# ChuanGanQi.net
KiCad netlist of a schematic drawn in Altium Designer
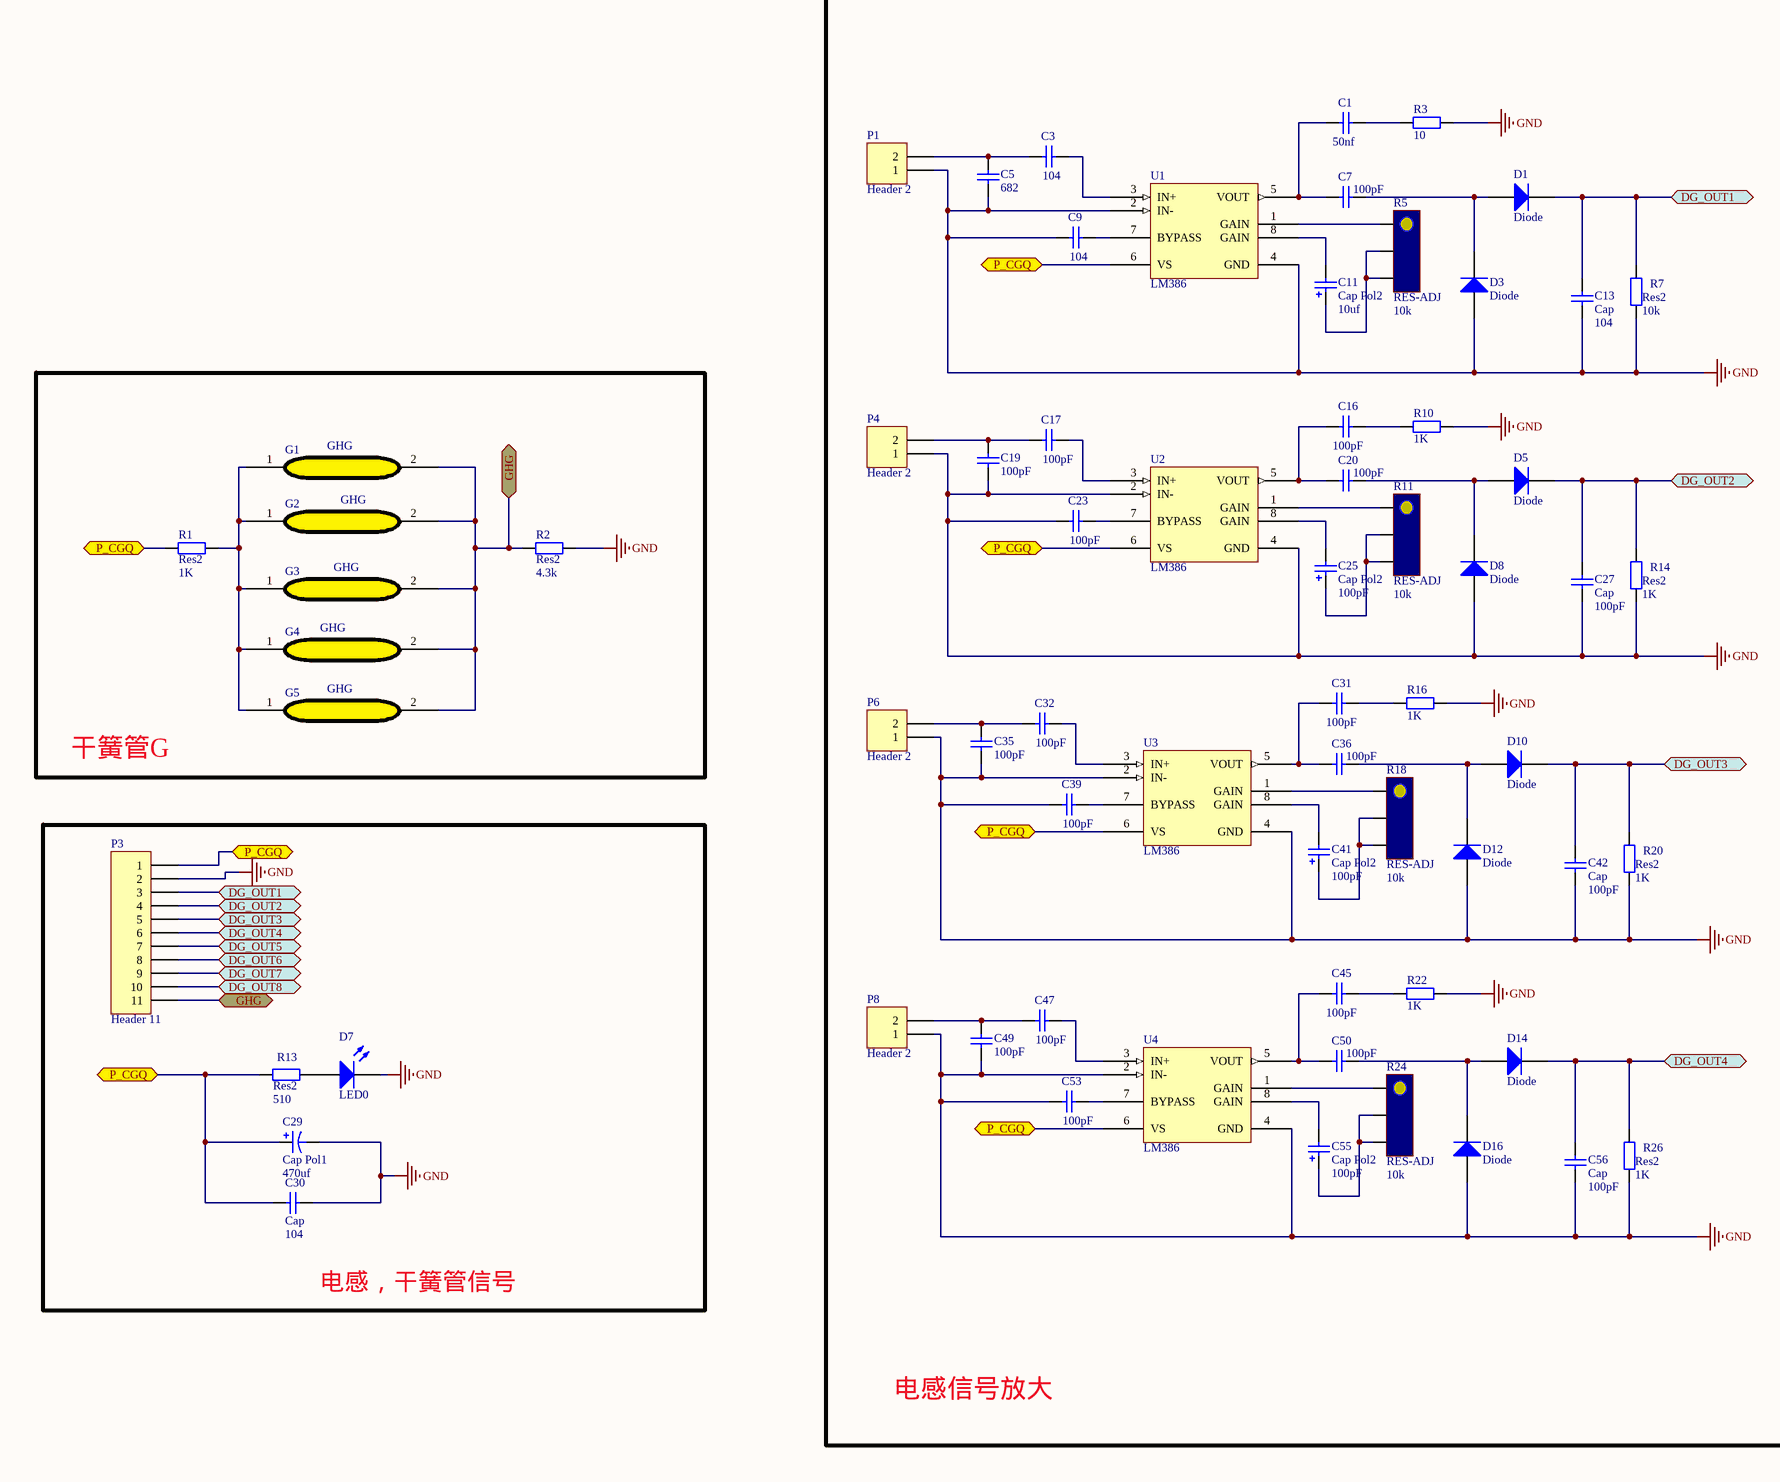
[diagram p0: ChuanGanQi.SchDoc, left]
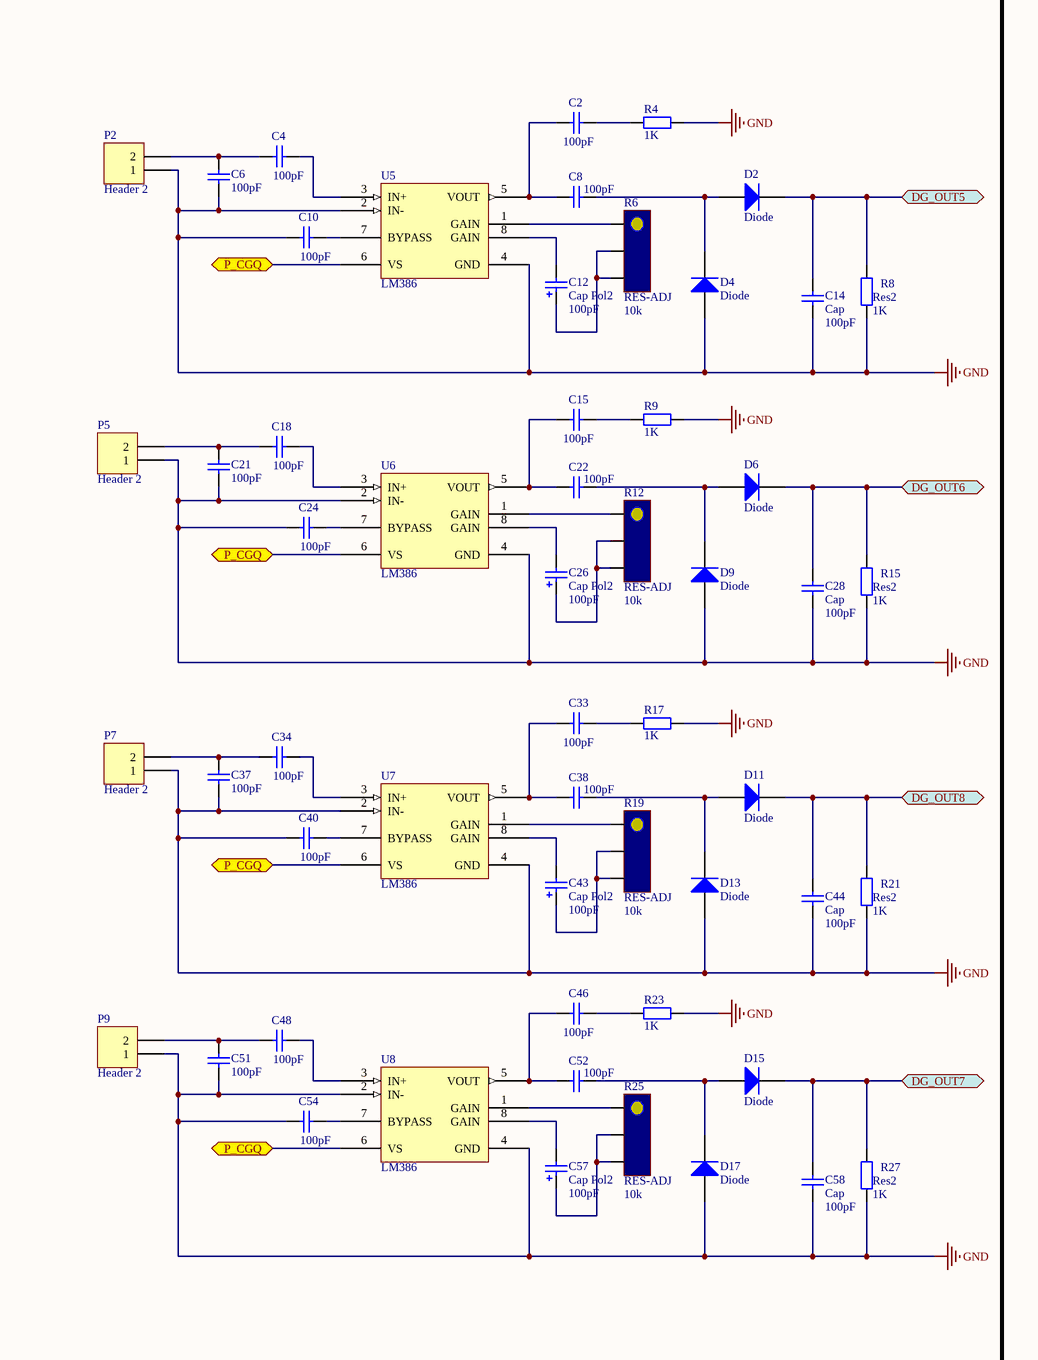
[diagram p1: ChuanGanQi.SchDoc, right]

(export (version "E")
  (design (tool "Eeschema 10.0.6"))
  (components
    (comp (ref "C1")
      (value "50nf")
      (footprint "C-0805")
      (description "Capacitor")
      (fields (field (name "Comment") "Cap"))
      (libsource (lib "Miscellaneous Devices") (part "Cap"))
    )
    (comp (ref "C2")
      (value "100pF")
      (footprint "C-0805")
      (description "Capacitor")
      (fields (field (name "Comment") "Cap"))
      (libsource (lib "Miscellaneous Devices") (part "Cap"))
    )
    (comp (ref "C3")
      (value "104")
      (footprint "C-0805")
      (description "Capacitor")
      (fields (field (name "Comment") "Cap"))
      (libsource (lib "Miscellaneous Devices") (part "Cap"))
    )
    (comp (ref "C4")
      (value "100pF")
      (footprint "C-0805")
      (description "Capacitor")
      (fields (field (name "Comment") "Cap"))
      (libsource (lib "Miscellaneous Devices") (part "Cap"))
    )
    (comp (ref "C5")
      (value "682")
      (footprint "C-0805")
      (description "Capacitor")
      (fields (field (name "Comment") "Cap"))
      (libsource (lib "Miscellaneous Devices") (part "Cap"))
    )
    (comp (ref "C6")
      (value "100pF")
      (footprint "C-0805")
      (description "Capacitor")
      (fields (field (name "Comment") "Cap"))
      (libsource (lib "Miscellaneous Devices") (part "Cap"))
    )
    (comp (ref "C7")
      (value "100pF")
      (footprint "C-0805")
      (description "Capacitor")
      (fields (field (name "Comment") "Cap"))
      (libsource (lib "Miscellaneous Devices") (part "Cap"))
    )
    (comp (ref "C8")
      (value "100pF")
      (footprint "C-0805")
      (description "Capacitor")
      (fields (field (name "Comment") "Cap"))
      (libsource (lib "Miscellaneous Devices") (part "Cap"))
    )
    (comp (ref "C9")
      (value "104")
      (footprint "C-0805")
      (description "Capacitor")
      (fields (field (name "Comment") "Cap"))
      (libsource (lib "Miscellaneous Devices") (part "Cap"))
    )
    (comp (ref "C10")
      (value "100pF")
      (footprint "C-0805")
      (description "Capacitor")
      (fields (field (name "Comment") "Cap"))
      (libsource (lib "Miscellaneous Devices") (part "Cap"))
    )
    (comp (ref "C11")
      (value "Cap Pol2")
      (footprint "C-0805")
      (description "Polarized Capacitor (Axial)")
      (fields (field (name "ALTIUM_VALUE") "10uf"))
      (libsource (lib "Miscellaneous Devices") (part "Cap Pol2"))
    )
    (comp (ref "C12")
      (value "Cap Pol2")
      (footprint "C-0805")
      (description "Polarized Capacitor (Axial)")
      (fields (field (name "ALTIUM_VALUE") "100pF"))
      (libsource (lib "Miscellaneous Devices") (part "Cap Pol2"))
    )
    (comp (ref "C13")
      (value "Cap")
      (footprint "C-0805")
      (description "Capacitor")
      (fields (field (name "ALTIUM_VALUE") "104"))
      (libsource (lib "Miscellaneous Devices") (part "Cap"))
    )
    (comp (ref "C14")
      (value "Cap")
      (footprint "C-0805")
      (description "Capacitor")
      (fields (field (name "ALTIUM_VALUE") "100pF"))
      (libsource (lib "Miscellaneous Devices") (part "Cap"))
    )
    (comp (ref "C15")
      (value "100pF")
      (footprint "C-0805")
      (description "Capacitor")
      (fields (field (name "Comment") "Cap"))
      (libsource (lib "Miscellaneous Devices") (part "Cap"))
    )
    (comp (ref "C16")
      (value "100pF")
      (footprint "C-0805")
      (description "Capacitor")
      (fields (field (name "Comment") "Cap"))
      (libsource (lib "Miscellaneous Devices") (part "Cap"))
    )
    (comp (ref "C17")
      (value "100pF")
      (footprint "C-0805")
      (description "Capacitor")
      (fields (field (name "Comment") "Cap"))
      (libsource (lib "Miscellaneous Devices") (part "Cap"))
    )
    (comp (ref "C18")
      (value "100pF")
      (footprint "C-0805")
      (description "Capacitor")
      (fields (field (name "Comment") "Cap"))
      (libsource (lib "Miscellaneous Devices") (part "Cap"))
    )
    (comp (ref "C19")
      (value "100pF")
      (footprint "C-0805")
      (description "Capacitor")
      (fields (field (name "Comment") "Cap"))
      (libsource (lib "Miscellaneous Devices") (part "Cap"))
    )
    (comp (ref "C20")
      (value "100pF")
      (footprint "C-0805")
      (description "Capacitor")
      (fields (field (name "Comment") "Cap"))
      (libsource (lib "Miscellaneous Devices") (part "Cap"))
    )
    (comp (ref "C21")
      (value "100pF")
      (footprint "C-0805")
      (description "Capacitor")
      (fields (field (name "Comment") "Cap"))
      (libsource (lib "Miscellaneous Devices") (part "Cap"))
    )
    (comp (ref "C22")
      (value "100pF")
      (footprint "C-0805")
      (description "Capacitor")
      (fields (field (name "Comment") "Cap"))
      (libsource (lib "Miscellaneous Devices") (part "Cap"))
    )
    (comp (ref "C23")
      (value "100pF")
      (footprint "C-0805")
      (description "Capacitor")
      (fields (field (name "Comment") "Cap"))
      (libsource (lib "Miscellaneous Devices") (part "Cap"))
    )
    (comp (ref "C24")
      (value "100pF")
      (footprint "C-0805")
      (description "Capacitor")
      (fields (field (name "Comment") "Cap"))
      (libsource (lib "Miscellaneous Devices") (part "Cap"))
    )
    (comp (ref "C25")
      (value "Cap Pol2")
      (footprint "C-0805")
      (description "Polarized Capacitor (Axial)")
      (fields (field (name "ALTIUM_VALUE") "100pF"))
      (libsource (lib "Miscellaneous Devices") (part "Cap Pol2"))
    )
    (comp (ref "C26")
      (value "Cap Pol2")
      (footprint "C-0805")
      (description "Polarized Capacitor (Axial)")
      (fields (field (name "ALTIUM_VALUE") "100pF"))
      (libsource (lib "Miscellaneous Devices") (part "Cap Pol2"))
    )
    (comp (ref "C27")
      (value "Cap")
      (footprint "C-0805")
      (description "Capacitor")
      (fields (field (name "ALTIUM_VALUE") "100pF"))
      (libsource (lib "Miscellaneous Devices") (part "Cap"))
    )
    (comp (ref "C28")
      (value "Cap")
      (footprint "C-0805")
      (description "Capacitor")
      (fields (field (name "ALTIUM_VALUE") "100pF"))
      (libsource (lib "Miscellaneous Devices") (part "Cap"))
    )
    (comp (ref "C29")
      (value "Cap Pol1")
      (footprint "1206")
      (description "Polarized Capacitor (Radial)")
      (fields (field (name "ALTIUM_VALUE") "470uf"))
      (libsource (lib "Miscellaneous Devices") (part "Cap Pol1"))
    )
    (comp (ref "C30")
      (value "Cap")
      (footprint "C-0805")
      (description "Capacitor")
      (fields (field (name "ALTIUM_VALUE") "104"))
      (libsource (lib "Miscellaneous Devices") (part "Cap"))
    )
    (comp (ref "C31")
      (value "100pF")
      (footprint "C-0805")
      (description "Capacitor")
      (fields (field (name "Comment") "Cap"))
      (libsource (lib "Miscellaneous Devices") (part "Cap"))
    )
    (comp (ref "C32")
      (value "100pF")
      (footprint "C-0805")
      (description "Capacitor")
      (fields (field (name "Comment") "Cap"))
      (libsource (lib "Miscellaneous Devices") (part "Cap"))
    )
    (comp (ref "C33")
      (value "100pF")
      (footprint "C-0805")
      (description "Capacitor")
      (fields (field (name "Comment") "Cap"))
      (libsource (lib "Miscellaneous Devices") (part "Cap"))
    )
    (comp (ref "C34")
      (value "100pF")
      (footprint "C-0805")
      (description "Capacitor")
      (fields (field (name "Comment") "Cap"))
      (libsource (lib "Miscellaneous Devices") (part "Cap"))
    )
    (comp (ref "C35")
      (value "100pF")
      (footprint "C-0805")
      (description "Capacitor")
      (fields (field (name "Comment") "Cap"))
      (libsource (lib "Miscellaneous Devices") (part "Cap"))
    )
    (comp (ref "C36")
      (value "100pF")
      (footprint "C-0805")
      (description "Capacitor")
      (fields (field (name "Comment") "Cap"))
      (libsource (lib "Miscellaneous Devices") (part "Cap"))
    )
    (comp (ref "C37")
      (value "100pF")
      (footprint "C-0805")
      (description "Capacitor")
      (fields (field (name "Comment") "Cap"))
      (libsource (lib "Miscellaneous Devices") (part "Cap"))
    )
    (comp (ref "C38")
      (value "100pF")
      (footprint "C-0805")
      (description "Capacitor")
      (fields (field (name "Comment") "Cap"))
      (libsource (lib "Miscellaneous Devices") (part "Cap"))
    )
    (comp (ref "C39")
      (value "100pF")
      (footprint "C-0805")
      (description "Capacitor")
      (fields (field (name "Comment") "Cap"))
      (libsource (lib "Miscellaneous Devices") (part "Cap"))
    )
    (comp (ref "C40")
      (value "100pF")
      (footprint "C-0805")
      (description "Capacitor")
      (fields (field (name "Comment") "Cap"))
      (libsource (lib "Miscellaneous Devices") (part "Cap"))
    )
    (comp (ref "C41")
      (value "Cap Pol2")
      (footprint "C-0805")
      (description "Polarized Capacitor (Axial)")
      (fields (field (name "ALTIUM_VALUE") "100pF"))
      (libsource (lib "Miscellaneous Devices") (part "Cap Pol2"))
    )
    (comp (ref "C42")
      (value "Cap")
      (footprint "C-0805")
      (description "Capacitor")
      (fields (field (name "ALTIUM_VALUE") "100pF"))
      (libsource (lib "Miscellaneous Devices") (part "Cap"))
    )
    (comp (ref "C43")
      (value "Cap Pol2")
      (footprint "C-0805")
      (description "Polarized Capacitor (Axial)")
      (fields (field (name "ALTIUM_VALUE") "100pF"))
      (libsource (lib "Miscellaneous Devices") (part "Cap Pol2"))
    )
    (comp (ref "C44")
      (value "Cap")
      (footprint "C-0805")
      (description "Capacitor")
      (fields (field (name "ALTIUM_VALUE") "100pF"))
      (libsource (lib "Miscellaneous Devices") (part "Cap"))
    )
    (comp (ref "C45")
      (value "100pF")
      (footprint "C-0805")
      (description "Capacitor")
      (fields (field (name "Comment") "Cap"))
      (libsource (lib "Miscellaneous Devices") (part "Cap"))
    )
    (comp (ref "C46")
      (value "100pF")
      (footprint "C-0805")
      (description "Capacitor")
      (fields (field (name "Comment") "Cap"))
      (libsource (lib "Miscellaneous Devices") (part "Cap"))
    )
    (comp (ref "C47")
      (value "100pF")
      (footprint "C-0805")
      (description "Capacitor")
      (fields (field (name "Comment") "Cap"))
      (libsource (lib "Miscellaneous Devices") (part "Cap"))
    )
    (comp (ref "C48")
      (value "100pF")
      (footprint "C-0805")
      (description "Capacitor")
      (fields (field (name "Comment") "Cap"))
      (libsource (lib "Miscellaneous Devices") (part "Cap"))
    )
    (comp (ref "C49")
      (value "100pF")
      (footprint "C-0805")
      (description "Capacitor")
      (fields (field (name "Comment") "Cap"))
      (libsource (lib "Miscellaneous Devices") (part "Cap"))
    )
    (comp (ref "C50")
      (value "100pF")
      (footprint "C-0805")
      (description "Capacitor")
      (fields (field (name "Comment") "Cap"))
      (libsource (lib "Miscellaneous Devices") (part "Cap"))
    )
    (comp (ref "C51")
      (value "100pF")
      (footprint "C-0805")
      (description "Capacitor")
      (fields (field (name "Comment") "Cap"))
      (libsource (lib "Miscellaneous Devices") (part "Cap"))
    )
    (comp (ref "C52")
      (value "100pF")
      (footprint "C-0805")
      (description "Capacitor")
      (fields (field (name "Comment") "Cap"))
      (libsource (lib "Miscellaneous Devices") (part "Cap"))
    )
    (comp (ref "C53")
      (value "100pF")
      (footprint "C-0805")
      (description "Capacitor")
      (fields (field (name "Comment") "Cap"))
      (libsource (lib "Miscellaneous Devices") (part "Cap"))
    )
    (comp (ref "C54")
      (value "100pF")
      (footprint "C-0805")
      (description "Capacitor")
      (fields (field (name "Comment") "Cap"))
      (libsource (lib "Miscellaneous Devices") (part "Cap"))
    )
    (comp (ref "C55")
      (value "Cap Pol2")
      (footprint "C-0805")
      (description "Polarized Capacitor (Axial)")
      (fields (field (name "ALTIUM_VALUE") "100pF"))
      (libsource (lib "Miscellaneous Devices") (part "Cap Pol2"))
    )
    (comp (ref "C56")
      (value "Cap")
      (footprint "C-0805")
      (description "Capacitor")
      (fields (field (name "ALTIUM_VALUE") "100pF"))
      (libsource (lib "Miscellaneous Devices") (part "Cap"))
    )
    (comp (ref "C57")
      (value "Cap Pol2")
      (footprint "C-0805")
      (description "Polarized Capacitor (Axial)")
      (fields (field (name "ALTIUM_VALUE") "100pF"))
      (libsource (lib "Miscellaneous Devices") (part "Cap Pol2"))
    )
    (comp (ref "C58")
      (value "Cap")
      (footprint "C-0805")
      (description "Capacitor")
      (fields (field (name "ALTIUM_VALUE") "100pF"))
      (libsource (lib "Miscellaneous Devices") (part "Cap"))
    )
    (comp (ref "D1")
      (value "Diode")
      (footprint "DO214AA")
      (description "Default Diode")
      (libsource (lib "Miscellaneous Devices") (part "Diode"))
    )
    (comp (ref "D2")
      (value "Diode")
      (footprint "DO214AA")
      (description "Default Diode")
      (libsource (lib "Miscellaneous Devices") (part "Diode"))
    )
    (comp (ref "D3")
      (value "Diode")
      (footprint "DO214AA")
      (description "Default Diode")
      (libsource (lib "Miscellaneous Devices") (part "Diode"))
    )
    (comp (ref "D4")
      (value "Diode")
      (footprint "DO214AA")
      (description "Default Diode")
      (libsource (lib "Miscellaneous Devices") (part "Diode"))
    )
    (comp (ref "D5")
      (value "Diode")
      (footprint "DO214AA")
      (description "Default Diode")
      (libsource (lib "Miscellaneous Devices") (part "Diode"))
    )
    (comp (ref "D6")
      (value "Diode")
      (footprint "DO214AA")
      (description "Default Diode")
      (libsource (lib "Miscellaneous Devices") (part "Diode"))
    )
    (comp (ref "D7")
      (value "LED0")
      (footprint "6-0805_N")
      (description "Typical INFRARED GaAs LED")
      (libsource (lib "Miscellaneous Devices") (part "LED0"))
    )
    (comp (ref "D8")
      (value "Diode")
      (footprint "DO214AA")
      (description "Default Diode")
      (libsource (lib "Miscellaneous Devices") (part "Diode"))
    )
    (comp (ref "D9")
      (value "Diode")
      (footprint "DO214AA")
      (description "Default Diode")
      (libsource (lib "Miscellaneous Devices") (part "Diode"))
    )
    (comp (ref "D10")
      (value "Diode")
      (footprint "DO214AA")
      (description "Default Diode")
      (libsource (lib "Miscellaneous Devices") (part "Diode"))
    )
    (comp (ref "D11")
      (value "Diode")
      (footprint "DO214AA")
      (description "Default Diode")
      (libsource (lib "Miscellaneous Devices") (part "Diode"))
    )
    (comp (ref "D12")
      (value "Diode")
      (footprint "DO214AA")
      (description "Default Diode")
      (libsource (lib "Miscellaneous Devices") (part "Diode"))
    )
    (comp (ref "D13")
      (value "Diode")
      (footprint "DO214AA")
      (description "Default Diode")
      (libsource (lib "Miscellaneous Devices") (part "Diode"))
    )
    (comp (ref "D14")
      (value "Diode")
      (footprint "DO214AA")
      (description "Default Diode")
      (libsource (lib "Miscellaneous Devices") (part "Diode"))
    )
    (comp (ref "D15")
      (value "Diode")
      (footprint "DO214AA")
      (description "Default Diode")
      (libsource (lib "Miscellaneous Devices") (part "Diode"))
    )
    (comp (ref "D16")
      (value "Diode")
      (footprint "DO214AA")
      (description "Default Diode")
      (libsource (lib "Miscellaneous Devices") (part "Diode"))
    )
    (comp (ref "D17")
      (value "Diode")
      (footprint "DO214AA")
      (description "Default Diode")
      (libsource (lib "Miscellaneous Devices") (part "Diode"))
    )
    (comp (ref "G1") (value "GHG") (footprint "GHG_MIN") (libsource (lib "常用封装") (part "GHG")))
    (comp (ref "G2") (value "GHG") (footprint "GHG_MIN") (libsource (lib "常用封装") (part "GHG")))
    (comp (ref "G3") (value "GHG") (footprint "GHG_MIN") (libsource (lib "常用封装") (part "GHG")))
    (comp (ref "G4") (value "GHG") (footprint "GHG_MIN") (libsource (lib "常用封装") (part "GHG")))
    (comp (ref "G5") (value "GHG") (footprint "GHG_MIN") (libsource (lib "常用封装") (part "GHG")))
    (comp (ref "P1")
      (value "Header 2")
      (footprint "HDR1X2")
      (description "Header, 2-Pin")
      (libsource (lib "Miscellaneous Connectors") (part "Header 2"))
    )
    (comp (ref "P2")
      (value "Header 2")
      (footprint "HDR1X2")
      (description "Header, 2-Pin")
      (libsource (lib "Miscellaneous Connectors") (part "Header 2"))
    )
    (comp (ref "P3")
      (value "Header 11")
      (footprint "HDR1X11")
      (description "Header, 11-Pin")
      (libsource (lib "Miscellaneous Connectors") (part "Header 11"))
    )
    (comp (ref "P4")
      (value "Header 2")
      (footprint "HDR1X2")
      (description "Header, 2-Pin")
      (libsource (lib "Miscellaneous Connectors") (part "Header 2"))
    )
    (comp (ref "P5")
      (value "Header 2")
      (footprint "HDR1X2")
      (description "Header, 2-Pin")
      (libsource (lib "Miscellaneous Connectors") (part "Header 2"))
    )
    (comp (ref "P6")
      (value "Header 2")
      (footprint "HDR1X2")
      (description "Header, 2-Pin")
      (libsource (lib "Miscellaneous Connectors") (part "Header 2"))
    )
    (comp (ref "P7")
      (value "Header 2")
      (footprint "HDR1X2")
      (description "Header, 2-Pin")
      (libsource (lib "Miscellaneous Connectors") (part "Header 2"))
    )
    (comp (ref "P8")
      (value "Header 2")
      (footprint "HDR1X2")
      (description "Header, 2-Pin")
      (libsource (lib "Miscellaneous Connectors") (part "Header 2"))
    )
    (comp (ref "P9")
      (value "Header 2")
      (footprint "HDR1X2")
      (description "Header, 2-Pin")
      (libsource (lib "Miscellaneous Connectors") (part "Header 2"))
    )
    (comp (ref "R1")
      (value "Res2")
      (footprint "0805")
      (description "Resistor")
      (fields (field (name "ALTIUM_VALUE") "1K"))
      (libsource (lib "Miscellaneous Devices") (part "Res2"))
    )
    (comp (ref "R2")
      (value "Res2")
      (footprint "0805")
      (description "Resistor")
      (fields (field (name "ALTIUM_VALUE") "4.3k"))
      (libsource (lib "Miscellaneous Devices") (part "Res2"))
    )
    (comp (ref "R3")
      (value "10")
      (footprint "0805")
      (description "Resistor")
      (fields (field (name "Comment") "Res2"))
      (libsource (lib "Miscellaneous Devices") (part "Res2"))
    )
    (comp (ref "R4")
      (value "1K")
      (footprint "0805")
      (description "Resistor")
      (fields (field (name "Comment") "Res2"))
      (libsource (lib "Miscellaneous Devices") (part "Res2"))
    )
    (comp (ref "R5")
      (value "RES-ADJ")
      (footprint "T-3224w")
      (fields (field (name "VELUE") "10k"))
      (libsource (lib "128飞思卡尔电路") (part "RES-ADJ"))
    )
    (comp (ref "R6")
      (value "RES-ADJ")
      (footprint "T-3224w")
      (fields (field (name "VELUE") "10k"))
      (libsource (lib "128飞思卡尔电路") (part "RES-ADJ"))
    )
    (comp (ref "R7")
      (value "Res2")
      (footprint "0805")
      (description "Resistor")
      (fields (field (name "ALTIUM_VALUE") "10k"))
      (libsource (lib "") (part "Res2_1"))
    )
    (comp (ref "R8")
      (value "Res2")
      (footprint "0805")
      (description "Resistor")
      (fields (field (name "ALTIUM_VALUE") "1K"))
      (libsource (lib "") (part "Res2_1"))
    )
    (comp (ref "R9")
      (value "1K")
      (footprint "0805")
      (description "Resistor")
      (fields (field (name "Comment") "Res2"))
      (libsource (lib "Miscellaneous Devices") (part "Res2"))
    )
    (comp (ref "R10")
      (value "1K")
      (footprint "0805")
      (description "Resistor")
      (fields (field (name "Comment") "Res2"))
      (libsource (lib "Miscellaneous Devices") (part "Res2"))
    )
    (comp (ref "R11")
      (value "RES-ADJ")
      (footprint "T-3224w")
      (fields (field (name "VELUE") "10k"))
      (libsource (lib "128飞思卡尔电路") (part "RES-ADJ"))
    )
    (comp (ref "R12")
      (value "RES-ADJ")
      (footprint "T-3224w")
      (fields (field (name "VELUE") "10k"))
      (libsource (lib "128飞思卡尔电路") (part "RES-ADJ"))
    )
    (comp (ref "R13")
      (value "Res2")
      (footprint "0805")
      (description "Resistor")
      (fields (field (name "ALTIUM_VALUE") "510"))
      (libsource (lib "Miscellaneous Devices") (part "Res2"))
    )
    (comp (ref "R14")
      (value "Res2")
      (footprint "0805")
      (description "Resistor")
      (fields (field (name "ALTIUM_VALUE") "1K"))
      (libsource (lib "") (part "Res2_1"))
    )
    (comp (ref "R15")
      (value "Res2")
      (footprint "0805")
      (description "Resistor")
      (fields (field (name "ALTIUM_VALUE") "1K"))
      (libsource (lib "") (part "Res2_1"))
    )
    (comp (ref "R16")
      (value "1K")
      (footprint "0805")
      (description "Resistor")
      (fields (field (name "Comment") "Res2"))
      (libsource (lib "Miscellaneous Devices") (part "Res2"))
    )
    (comp (ref "R17")
      (value "1K")
      (footprint "0805")
      (description "Resistor")
      (fields (field (name "Comment") "Res2"))
      (libsource (lib "Miscellaneous Devices") (part "Res2"))
    )
    (comp (ref "R18")
      (value "RES-ADJ")
      (footprint "T-3224w")
      (fields (field (name "VELUE") "10k"))
      (libsource (lib "128飞思卡尔电路") (part "RES-ADJ"))
    )
    (comp (ref "R19")
      (value "RES-ADJ")
      (footprint "T-3224w")
      (fields (field (name "VELUE") "10k"))
      (libsource (lib "128飞思卡尔电路") (part "RES-ADJ"))
    )
    (comp (ref "R20")
      (value "Res2")
      (footprint "0805")
      (description "Resistor")
      (fields (field (name "ALTIUM_VALUE") "1K"))
      (libsource (lib "") (part "Res2_1"))
    )
    (comp (ref "R21")
      (value "Res2")
      (footprint "0805")
      (description "Resistor")
      (fields (field (name "ALTIUM_VALUE") "1K"))
      (libsource (lib "") (part "Res2_1"))
    )
    (comp (ref "R22")
      (value "1K")
      (footprint "0805")
      (description "Resistor")
      (fields (field (name "Comment") "Res2"))
      (libsource (lib "Miscellaneous Devices") (part "Res2"))
    )
    (comp (ref "R23")
      (value "1K")
      (footprint "0805")
      (description "Resistor")
      (fields (field (name "Comment") "Res2"))
      (libsource (lib "Miscellaneous Devices") (part "Res2"))
    )
    (comp (ref "R24")
      (value "RES-ADJ")
      (footprint "T-3224w")
      (fields (field (name "VELUE") "10k"))
      (libsource (lib "128飞思卡尔电路") (part "RES-ADJ"))
    )
    (comp (ref "R25")
      (value "RES-ADJ")
      (footprint "T-3224w")
      (fields (field (name "VELUE") "10k"))
      (libsource (lib "128飞思卡尔电路") (part "RES-ADJ"))
    )
    (comp (ref "R26")
      (value "Res2")
      (footprint "0805")
      (description "Resistor")
      (fields (field (name "ALTIUM_VALUE") "1K"))
      (libsource (lib "") (part "Res2_1"))
    )
    (comp (ref "R27")
      (value "Res2")
      (footprint "0805")
      (description "Resistor")
      (fields (field (name "ALTIUM_VALUE") "1K"))
      (libsource (lib "") (part "Res2_1"))
    )
    (comp (ref "U1") (value "LM386") (footprint "SO-8") (libsource (lib "常用封装") (part "LM386")))
    (comp (ref "U2") (value "LM386") (footprint "SO-8") (libsource (lib "常用封装") (part "LM386")))
    (comp (ref "U3") (value "LM386") (footprint "SO-8") (libsource (lib "常用封装") (part "LM386")))
    (comp (ref "U4") (value "LM386") (footprint "SO-8") (libsource (lib "常用封装") (part "LM386")))
    (comp (ref "U5") (value "LM386") (footprint "SO-8") (libsource (lib "常用封装") (part "LM386")))
    (comp (ref "U6") (value "LM386") (footprint "SO-8") (libsource (lib "常用封装") (part "LM386")))
    (comp (ref "U7") (value "LM386") (footprint "SO-8") (libsource (lib "常用封装") (part "LM386")))
    (comp (ref "U8") (value "LM386") (footprint "SO-8") (libsource (lib "常用封装") (part "LM386")))
  )
  (nets
    (net (code "1") (name "/DG_OUT1") (class "Default")
      (node (ref "C13") (pin "2") (pinfunction "2_2") (pintype "passive"))
      (node (ref "D1") (pin "2") (pinfunction "K_2") (pintype "passive"))
      (node (ref "P3") (pin "3") (pinfunction "3_3") (pintype "passive"))
      (node (ref "R7") (pin "2") (pinfunction "2_2") (pintype "passive"))
    )
    (net (code "2") (name "/DG_OUT2") (class "Default")
      (node (ref "C27") (pin "2") (pinfunction "2_2") (pintype "passive"))
      (node (ref "D5") (pin "2") (pinfunction "K_2") (pintype "passive"))
      (node (ref "P3") (pin "4") (pinfunction "4_4") (pintype "passive"))
      (node (ref "R14") (pin "2") (pinfunction "2_2") (pintype "passive"))
    )
    (net (code "3") (name "/DG_OUT3") (class "Default")
      (node (ref "C42") (pin "2") (pinfunction "2_2") (pintype "passive"))
      (node (ref "D10") (pin "2") (pinfunction "K_2") (pintype "passive"))
      (node (ref "P3") (pin "5") (pinfunction "5_5") (pintype "passive"))
      (node (ref "R20") (pin "2") (pinfunction "2_2") (pintype "passive"))
    )
    (net (code "4") (name "/DG_OUT4") (class "Default")
      (node (ref "C56") (pin "2") (pinfunction "2_2") (pintype "passive"))
      (node (ref "D14") (pin "2") (pinfunction "K_2") (pintype "passive"))
      (node (ref "P3") (pin "6") (pinfunction "6_6") (pintype "passive"))
      (node (ref "R26") (pin "2") (pinfunction "2_2") (pintype "passive"))
    )
    (net (code "5") (name "/DG_OUT5") (class "Default")
      (node (ref "C14") (pin "2") (pinfunction "2_2") (pintype "passive"))
      (node (ref "D2") (pin "2") (pinfunction "K_2") (pintype "passive"))
      (node (ref "P3") (pin "7") (pinfunction "7_7") (pintype "passive"))
      (node (ref "R8") (pin "2") (pinfunction "2_2") (pintype "passive"))
    )
    (net (code "6") (name "/DG_OUT6") (class "Default")
      (node (ref "C28") (pin "2") (pinfunction "2_2") (pintype "passive"))
      (node (ref "D6") (pin "2") (pinfunction "K_2") (pintype "passive"))
      (node (ref "P3") (pin "8") (pinfunction "8_8") (pintype "passive"))
      (node (ref "R15") (pin "2") (pinfunction "2_2") (pintype "passive"))
    )
    (net (code "7") (name "/DG_OUT7") (class "Default")
      (node (ref "C58") (pin "2") (pinfunction "2_2") (pintype "passive"))
      (node (ref "D15") (pin "2") (pinfunction "K_2") (pintype "passive"))
      (node (ref "P3") (pin "9") (pinfunction "9_9") (pintype "passive"))
      (node (ref "R27") (pin "2") (pinfunction "2_2") (pintype "passive"))
    )
    (net (code "8") (name "/DG_OUT8") (class "Default")
      (node (ref "C44") (pin "2") (pinfunction "2_2") (pintype "passive"))
      (node (ref "D11") (pin "2") (pinfunction "K_2") (pintype "passive"))
      (node (ref "P3") (pin "10") (pinfunction "10_10") (pintype "passive"))
      (node (ref "R21") (pin "2") (pinfunction "2_2") (pintype "passive"))
    )
    (net (code "9") (name "/GHG") (class "Default")
      (node (ref "G1") (pin "2") (pinfunction "PIN_2") (pintype "passive"))
      (node (ref "G2") (pin "2") (pinfunction "PIN_2") (pintype "passive"))
      (node (ref "G3") (pin "2") (pinfunction "PIN_2") (pintype "passive"))
      (node (ref "G4") (pin "2") (pinfunction "PIN_2") (pintype "passive"))
      (node (ref "G5") (pin "2") (pinfunction "PIN_2") (pintype "passive"))
      (node (ref "P3") (pin "11") (pinfunction "11_11") (pintype "passive"))
      (node (ref "R2") (pin "1") (pinfunction "1_1") (pintype "passive"))
    )
    (net (code "10") (name "/P_CGQ") (class "Default")
      (node (ref "C29") (pin "1") (pinfunction "1_1") (pintype "passive"))
      (node (ref "C30") (pin "2") (pinfunction "2_2") (pintype "passive"))
      (node (ref "P3") (pin "1") (pinfunction "1_1") (pintype "passive"))
      (node (ref "R1") (pin "1") (pinfunction "1_1") (pintype "passive"))
      (node (ref "R13") (pin "1") (pinfunction "1_1") (pintype "passive"))
      (node (ref "U1") (pin "6") (pinfunction "VS_6") (pintype "passive"))
      (node (ref "U2") (pin "6") (pinfunction "VS_6") (pintype "passive"))
      (node (ref "U3") (pin "6") (pinfunction "VS_6") (pintype "passive"))
      (node (ref "U4") (pin "6") (pinfunction "VS_6") (pintype "passive"))
      (node (ref "U5") (pin "6") (pinfunction "VS_6") (pintype "passive"))
      (node (ref "U6") (pin "6") (pinfunction "VS_6") (pintype "passive"))
      (node (ref "U7") (pin "6") (pinfunction "VS_6") (pintype "passive"))
      (node (ref "U8") (pin "6") (pinfunction "VS_6") (pintype "passive"))
    )
    (net (code "11") (name "GND") (class "Default")
      (node (ref "C10") (pin "1") (pinfunction "1_1") (pintype "passive"))
      (node (ref "C13") (pin "1") (pinfunction "1_1") (pintype "passive"))
      (node (ref "C14") (pin "1") (pinfunction "1_1") (pintype "passive"))
      (node (ref "C19") (pin "1") (pinfunction "1_1") (pintype "passive"))
      (node (ref "C21") (pin "1") (pinfunction "1_1") (pintype "passive"))
      (node (ref "C23") (pin "1") (pinfunction "1_1") (pintype "passive"))
      (node (ref "C24") (pin "1") (pinfunction "1_1") (pintype "passive"))
      (node (ref "C27") (pin "1") (pinfunction "1_1") (pintype "passive"))
      (node (ref "C28") (pin "1") (pinfunction "1_1") (pintype "passive"))
      (node (ref "C29") (pin "2") (pinfunction "2_2") (pintype "passive"))
      (node (ref "C30") (pin "1") (pinfunction "1_1") (pintype "passive"))
      (node (ref "C35") (pin "1") (pinfunction "1_1") (pintype "passive"))
      (node (ref "C37") (pin "1") (pinfunction "1_1") (pintype "passive"))
      (node (ref "C39") (pin "1") (pinfunction "1_1") (pintype "passive"))
      (node (ref "C40") (pin "1") (pinfunction "1_1") (pintype "passive"))
      (node (ref "C42") (pin "1") (pinfunction "1_1") (pintype "passive"))
      (node (ref "C44") (pin "1") (pinfunction "1_1") (pintype "passive"))
      (node (ref "C49") (pin "1") (pinfunction "1_1") (pintype "passive"))
      (node (ref "C5") (pin "1") (pinfunction "1_1") (pintype "passive"))
      (node (ref "C51") (pin "1") (pinfunction "1_1") (pintype "passive"))
      (node (ref "C53") (pin "1") (pinfunction "1_1") (pintype "passive"))
      (node (ref "C54") (pin "1") (pinfunction "1_1") (pintype "passive"))
      (node (ref "C56") (pin "1") (pinfunction "1_1") (pintype "passive"))
      (node (ref "C58") (pin "1") (pinfunction "1_1") (pintype "passive"))
      (node (ref "C6") (pin "1") (pinfunction "1_1") (pintype "passive"))
      (node (ref "C9") (pin "1") (pinfunction "1_1") (pintype "passive"))
      (node (ref "D12") (pin "1") (pinfunction "A_1") (pintype "passive"))
      (node (ref "D13") (pin "1") (pinfunction "A_1") (pintype "passive"))
      (node (ref "D16") (pin "1") (pinfunction "A_1") (pintype "passive"))
      (node (ref "D17") (pin "1") (pinfunction "A_1") (pintype "passive"))
      (node (ref "D3") (pin "1") (pinfunction "A_1") (pintype "passive"))
      (node (ref "D4") (pin "1") (pinfunction "A_1") (pintype "passive"))
      (node (ref "D7") (pin "2") (pinfunction "K_2") (pintype "passive"))
      (node (ref "D8") (pin "1") (pinfunction "A_1") (pintype "passive"))
      (node (ref "D9") (pin "1") (pinfunction "A_1") (pintype "passive"))
      (node (ref "P1") (pin "1") (pinfunction "1_1") (pintype "passive"))
      (node (ref "P2") (pin "1") (pinfunction "1_1") (pintype "passive"))
      (node (ref "P3") (pin "2") (pinfunction "2_2") (pintype "passive"))
      (node (ref "P4") (pin "1") (pinfunction "1_1") (pintype "passive"))
      (node (ref "P5") (pin "1") (pinfunction "1_1") (pintype "passive"))
      (node (ref "P6") (pin "1") (pinfunction "1_1") (pintype "passive"))
      (node (ref "P7") (pin "1") (pinfunction "1_1") (pintype "passive"))
      (node (ref "P8") (pin "1") (pinfunction "1_1") (pintype "passive"))
      (node (ref "P9") (pin "1") (pinfunction "1_1") (pintype "passive"))
      (node (ref "R10") (pin "2") (pinfunction "2_2") (pintype "passive"))
      (node (ref "R14") (pin "1") (pinfunction "1_1") (pintype "passive"))
      (node (ref "R15") (pin "1") (pinfunction "1_1") (pintype "passive"))
      (node (ref "R16") (pin "2") (pinfunction "2_2") (pintype "passive"))
      (node (ref "R17") (pin "2") (pinfunction "2_2") (pintype "passive"))
      (node (ref "R2") (pin "2") (pinfunction "2_2") (pintype "passive"))
      (node (ref "R20") (pin "1") (pinfunction "1_1") (pintype "passive"))
      (node (ref "R21") (pin "1") (pinfunction "1_1") (pintype "passive"))
      (node (ref "R22") (pin "2") (pinfunction "2_2") (pintype "passive"))
      (node (ref "R23") (pin "2") (pinfunction "2_2") (pintype "passive"))
      (node (ref "R26") (pin "1") (pinfunction "1_1") (pintype "passive"))
      (node (ref "R27") (pin "1") (pinfunction "1_1") (pintype "passive"))
      (node (ref "R3") (pin "2") (pinfunction "2_2") (pintype "passive"))
      (node (ref "R4") (pin "2") (pinfunction "2_2") (pintype "passive"))
      (node (ref "R7") (pin "1") (pinfunction "1_1") (pintype "passive"))
      (node (ref "R8") (pin "1") (pinfunction "1_1") (pintype "passive"))
      (node (ref "R9") (pin "2") (pinfunction "2_2") (pintype "passive"))
      (node (ref "U1") (pin "2") (pinfunction "IN-_2") (pintype "input"))
      (node (ref "U1") (pin "4") (pinfunction "GND_4") (pintype "passive"))
      (node (ref "U2") (pin "2") (pinfunction "IN-_2") (pintype "input"))
      (node (ref "U2") (pin "4") (pinfunction "GND_4") (pintype "passive"))
      (node (ref "U3") (pin "2") (pinfunction "IN-_2") (pintype "input"))
      (node (ref "U3") (pin "4") (pinfunction "GND_4") (pintype "passive"))
      (node (ref "U4") (pin "2") (pinfunction "IN-_2") (pintype "input"))
      (node (ref "U4") (pin "4") (pinfunction "GND_4") (pintype "passive"))
      (node (ref "U5") (pin "2") (pinfunction "IN-_2") (pintype "input"))
      (node (ref "U5") (pin "4") (pinfunction "GND_4") (pintype "passive"))
      (node (ref "U6") (pin "2") (pinfunction "IN-_2") (pintype "input"))
      (node (ref "U6") (pin "4") (pinfunction "GND_4") (pintype "passive"))
      (node (ref "U7") (pin "2") (pinfunction "IN-_2") (pintype "input"))
      (node (ref "U7") (pin "4") (pinfunction "GND_4") (pintype "passive"))
      (node (ref "U8") (pin "2") (pinfunction "IN-_2") (pintype "input"))
      (node (ref "U8") (pin "4") (pinfunction "GND_4") (pintype "passive"))
    )
    (net (code "12") (name "Net-(C1-Pad2)") (class "Default")
      (node (ref "C1") (pin "2") (pinfunction "2_2") (pintype "passive"))
      (node (ref "R3") (pin "1") (pinfunction "1_1") (pintype "passive"))
    )
    (net (code "13") (name "Net-(C2-Pad2)") (class "Default")
      (node (ref "C2") (pin "2") (pinfunction "2_2") (pintype "passive"))
      (node (ref "R4") (pin "1") (pinfunction "1_1") (pintype "passive"))
    )
    (net (code "14") (name "Net-(C3-Pad1)") (class "Default")
      (node (ref "C3") (pin "1") (pinfunction "1_1") (pintype "passive"))
      (node (ref "C5") (pin "2") (pinfunction "2_2") (pintype "passive"))
      (node (ref "P1") (pin "2") (pinfunction "2_2") (pintype "passive"))
    )
    (net (code "15") (name "Net-(C4-Pad1)") (class "Default")
      (node (ref "C4") (pin "1") (pinfunction "1_1") (pintype "passive"))
      (node (ref "C6") (pin "2") (pinfunction "2_2") (pintype "passive"))
      (node (ref "P2") (pin "2") (pinfunction "2_2") (pintype "passive"))
    )
    (net (code "16") (name "Net-(C11-Pad1)") (class "Default")
      (node (ref "C11") (pin "1") (pinfunction "1_1") (pintype "passive"))
      (node (ref "R5") (pin "1") (pinfunction "1_1") (pintype "passive"))
      (node (ref "R5") (pin "2") (pinfunction "2_2") (pintype "passive"))
    )
    (net (code "17") (name "Net-(C11-Pad2)") (class "Default")
      (node (ref "C11") (pin "2") (pinfunction "2_2") (pintype "passive"))
      (node (ref "U1") (pin "8") (pinfunction "GAIN_8") (pintype "passive"))
    )
    (net (code "18") (name "Net-(C12-Pad1)") (class "Default")
      (node (ref "C12") (pin "1") (pinfunction "1_1") (pintype "passive"))
      (node (ref "R6") (pin "1") (pinfunction "1_1") (pintype "passive"))
      (node (ref "R6") (pin "2") (pinfunction "2_2") (pintype "passive"))
    )
    (net (code "19") (name "Net-(C12-Pad2)") (class "Default")
      (node (ref "C12") (pin "2") (pinfunction "2_2") (pintype "passive"))
      (node (ref "U5") (pin "8") (pinfunction "GAIN_8") (pintype "passive"))
    )
    (net (code "20") (name "Net-(C15-Pad2)") (class "Default")
      (node (ref "C15") (pin "2") (pinfunction "2_2") (pintype "passive"))
      (node (ref "R9") (pin "1") (pinfunction "1_1") (pintype "passive"))
    )
    (net (code "21") (name "Net-(C16-Pad2)") (class "Default")
      (node (ref "C16") (pin "2") (pinfunction "2_2") (pintype "passive"))
      (node (ref "R10") (pin "1") (pinfunction "1_1") (pintype "passive"))
    )
    (net (code "22") (name "Net-(C17-Pad1)") (class "Default")
      (node (ref "C17") (pin "1") (pinfunction "1_1") (pintype "passive"))
      (node (ref "C19") (pin "2") (pinfunction "2_2") (pintype "passive"))
      (node (ref "P4") (pin "2") (pinfunction "2_2") (pintype "passive"))
    )
    (net (code "23") (name "Net-(C18-Pad1)") (class "Default")
      (node (ref "C18") (pin "1") (pinfunction "1_1") (pintype "passive"))
      (node (ref "C21") (pin "2") (pinfunction "2_2") (pintype "passive"))
      (node (ref "P5") (pin "2") (pinfunction "2_2") (pintype "passive"))
    )
    (net (code "24") (name "Net-(C25-Pad1)") (class "Default")
      (node (ref "C25") (pin "1") (pinfunction "1_1") (pintype "passive"))
      (node (ref "R11") (pin "1") (pinfunction "1_1") (pintype "passive"))
      (node (ref "R11") (pin "2") (pinfunction "2_2") (pintype "passive"))
    )
    (net (code "25") (name "Net-(C25-Pad2)") (class "Default")
      (node (ref "C25") (pin "2") (pinfunction "2_2") (pintype "passive"))
      (node (ref "U2") (pin "8") (pinfunction "GAIN_8") (pintype "passive"))
    )
    (net (code "26") (name "Net-(C26-Pad1)") (class "Default")
      (node (ref "C26") (pin "1") (pinfunction "1_1") (pintype "passive"))
      (node (ref "R12") (pin "1") (pinfunction "1_1") (pintype "passive"))
      (node (ref "R12") (pin "2") (pinfunction "2_2") (pintype "passive"))
    )
    (net (code "27") (name "Net-(C26-Pad2)") (class "Default")
      (node (ref "C26") (pin "2") (pinfunction "2_2") (pintype "passive"))
      (node (ref "U6") (pin "8") (pinfunction "GAIN_8") (pintype "passive"))
    )
    (net (code "28") (name "Net-(C31-Pad2)") (class "Default")
      (node (ref "C31") (pin "2") (pinfunction "2_2") (pintype "passive"))
      (node (ref "R16") (pin "1") (pinfunction "1_1") (pintype "passive"))
    )
    (net (code "29") (name "Net-(C32-Pad1)") (class "Default")
      (node (ref "C32") (pin "1") (pinfunction "1_1") (pintype "passive"))
      (node (ref "C35") (pin "2") (pinfunction "2_2") (pintype "passive"))
      (node (ref "P6") (pin "2") (pinfunction "2_2") (pintype "passive"))
    )
    (net (code "30") (name "Net-(C33-Pad2)") (class "Default")
      (node (ref "C33") (pin "2") (pinfunction "2_2") (pintype "passive"))
      (node (ref "R17") (pin "1") (pinfunction "1_1") (pintype "passive"))
    )
    (net (code "31") (name "Net-(C34-Pad1)") (class "Default")
      (node (ref "C34") (pin "1") (pinfunction "1_1") (pintype "passive"))
      (node (ref "C37") (pin "2") (pinfunction "2_2") (pintype "passive"))
      (node (ref "P7") (pin "2") (pinfunction "2_2") (pintype "passive"))
    )
    (net (code "32") (name "Net-(C41-Pad1)") (class "Default")
      (node (ref "C41") (pin "1") (pinfunction "1_1") (pintype "passive"))
      (node (ref "R18") (pin "1") (pinfunction "1_1") (pintype "passive"))
      (node (ref "R18") (pin "2") (pinfunction "2_2") (pintype "passive"))
    )
    (net (code "33") (name "Net-(C41-Pad2)") (class "Default")
      (node (ref "C41") (pin "2") (pinfunction "2_2") (pintype "passive"))
      (node (ref "U3") (pin "8") (pinfunction "GAIN_8") (pintype "passive"))
    )
    (net (code "34") (name "Net-(C43-Pad1)") (class "Default")
      (node (ref "C43") (pin "1") (pinfunction "1_1") (pintype "passive"))
      (node (ref "R19") (pin "1") (pinfunction "1_1") (pintype "passive"))
      (node (ref "R19") (pin "2") (pinfunction "2_2") (pintype "passive"))
    )
    (net (code "35") (name "Net-(C43-Pad2)") (class "Default")
      (node (ref "C43") (pin "2") (pinfunction "2_2") (pintype "passive"))
      (node (ref "U7") (pin "8") (pinfunction "GAIN_8") (pintype "passive"))
    )
    (net (code "36") (name "Net-(C45-Pad2)") (class "Default")
      (node (ref "C45") (pin "2") (pinfunction "2_2") (pintype "passive"))
      (node (ref "R22") (pin "1") (pinfunction "1_1") (pintype "passive"))
    )
    (net (code "37") (name "Net-(C46-Pad2)") (class "Default")
      (node (ref "C46") (pin "2") (pinfunction "2_2") (pintype "passive"))
      (node (ref "R23") (pin "1") (pinfunction "1_1") (pintype "passive"))
    )
    (net (code "38") (name "Net-(C47-Pad1)") (class "Default")
      (node (ref "C47") (pin "1") (pinfunction "1_1") (pintype "passive"))
      (node (ref "C49") (pin "2") (pinfunction "2_2") (pintype "passive"))
      (node (ref "P8") (pin "2") (pinfunction "2_2") (pintype "passive"))
    )
    (net (code "39") (name "Net-(C48-Pad1)") (class "Default")
      (node (ref "C48") (pin "1") (pinfunction "1_1") (pintype "passive"))
      (node (ref "C51") (pin "2") (pinfunction "2_2") (pintype "passive"))
      (node (ref "P9") (pin "2") (pinfunction "2_2") (pintype "passive"))
    )
    (net (code "40") (name "Net-(C55-Pad1)") (class "Default")
      (node (ref "C55") (pin "1") (pinfunction "1_1") (pintype "passive"))
      (node (ref "R24") (pin "1") (pinfunction "1_1") (pintype "passive"))
      (node (ref "R24") (pin "2") (pinfunction "2_2") (pintype "passive"))
    )
    (net (code "41") (name "Net-(C55-Pad2)") (class "Default")
      (node (ref "C55") (pin "2") (pinfunction "2_2") (pintype "passive"))
      (node (ref "U4") (pin "8") (pinfunction "GAIN_8") (pintype "passive"))
    )
    (net (code "42") (name "Net-(C57-Pad1)") (class "Default")
      (node (ref "C57") (pin "1") (pinfunction "1_1") (pintype "passive"))
      (node (ref "R25") (pin "1") (pinfunction "1_1") (pintype "passive"))
      (node (ref "R25") (pin "2") (pinfunction "2_2") (pintype "passive"))
    )
    (net (code "43") (name "Net-(C57-Pad2)") (class "Default")
      (node (ref "C57") (pin "2") (pinfunction "2_2") (pintype "passive"))
      (node (ref "U8") (pin "8") (pinfunction "GAIN_8") (pintype "passive"))
    )
    (net (code "44") (name "Net-(D1-A)") (class "Default")
      (node (ref "C7") (pin "1") (pinfunction "1_1") (pintype "passive"))
      (node (ref "D1") (pin "1") (pinfunction "A_1") (pintype "passive"))
      (node (ref "D3") (pin "2") (pinfunction "K_2") (pintype "passive"))
    )
    (net (code "45") (name "Net-(D2-A)") (class "Default")
      (node (ref "C8") (pin "1") (pinfunction "1_1") (pintype "passive"))
      (node (ref "D2") (pin "1") (pinfunction "A_1") (pintype "passive"))
      (node (ref "D4") (pin "2") (pinfunction "K_2") (pintype "passive"))
    )
    (net (code "46") (name "Net-(D5-A)") (class "Default")
      (node (ref "C20") (pin "1") (pinfunction "1_1") (pintype "passive"))
      (node (ref "D5") (pin "1") (pinfunction "A_1") (pintype "passive"))
      (node (ref "D8") (pin "2") (pinfunction "K_2") (pintype "passive"))
    )
    (net (code "47") (name "Net-(D6-A)") (class "Default")
      (node (ref "C22") (pin "1") (pinfunction "1_1") (pintype "passive"))
      (node (ref "D6") (pin "1") (pinfunction "A_1") (pintype "passive"))
      (node (ref "D9") (pin "2") (pinfunction "K_2") (pintype "passive"))
    )
    (net (code "48") (name "Net-(D7-A)") (class "Default")
      (node (ref "D7") (pin "1") (pinfunction "A_1") (pintype "passive"))
      (node (ref "R13") (pin "2") (pinfunction "2_2") (pintype "passive"))
    )
    (net (code "49") (name "Net-(D10-A)") (class "Default")
      (node (ref "C36") (pin "1") (pinfunction "1_1") (pintype "passive"))
      (node (ref "D10") (pin "1") (pinfunction "A_1") (pintype "passive"))
      (node (ref "D12") (pin "2") (pinfunction "K_2") (pintype "passive"))
    )
    (net (code "50") (name "Net-(D11-A)") (class "Default")
      (node (ref "C38") (pin "1") (pinfunction "1_1") (pintype "passive"))
      (node (ref "D11") (pin "1") (pinfunction "A_1") (pintype "passive"))
      (node (ref "D13") (pin "2") (pinfunction "K_2") (pintype "passive"))
    )
    (net (code "51") (name "Net-(D14-A)") (class "Default")
      (node (ref "C50") (pin "1") (pinfunction "1_1") (pintype "passive"))
      (node (ref "D14") (pin "1") (pinfunction "A_1") (pintype "passive"))
      (node (ref "D16") (pin "2") (pinfunction "K_2") (pintype "passive"))
    )
    (net (code "52") (name "Net-(D15-A)") (class "Default")
      (node (ref "C52") (pin "1") (pinfunction "1_1") (pintype "passive"))
      (node (ref "D15") (pin "1") (pinfunction "A_1") (pintype "passive"))
      (node (ref "D17") (pin "2") (pinfunction "K_2") (pintype "passive"))
    )
    (net (code "53") (name "Net-(G1-PIN-Pad1)") (class "Default")
      (node (ref "G1") (pin "1") (pinfunction "PIN_1") (pintype "passive"))
      (node (ref "G2") (pin "1") (pinfunction "PIN_1") (pintype "passive"))
      (node (ref "G3") (pin "1") (pinfunction "PIN_1") (pintype "passive"))
      (node (ref "G4") (pin "1") (pinfunction "PIN_1") (pintype "passive"))
      (node (ref "G5") (pin "1") (pinfunction "PIN_1") (pintype "passive"))
      (node (ref "R1") (pin "2") (pinfunction "2_2") (pintype "passive"))
    )
    (net (code "54") (name "Net-(R5-Pad3)") (class "Default")
      (node (ref "R5") (pin "3") (pinfunction "3_3") (pintype "passive"))
      (node (ref "U1") (pin "1") (pinfunction "GAIN_1") (pintype "passive"))
    )
    (net (code "55") (name "Net-(R6-Pad3)") (class "Default")
      (node (ref "R6") (pin "3") (pinfunction "3_3") (pintype "passive"))
      (node (ref "U5") (pin "1") (pinfunction "GAIN_1") (pintype "passive"))
    )
    (net (code "56") (name "Net-(R11-Pad3)") (class "Default")
      (node (ref "R11") (pin "3") (pinfunction "3_3") (pintype "passive"))
      (node (ref "U2") (pin "1") (pinfunction "GAIN_1") (pintype "passive"))
    )
    (net (code "57") (name "Net-(R12-Pad3)") (class "Default")
      (node (ref "R12") (pin "3") (pinfunction "3_3") (pintype "passive"))
      (node (ref "U6") (pin "1") (pinfunction "GAIN_1") (pintype "passive"))
    )
    (net (code "58") (name "Net-(R18-Pad3)") (class "Default")
      (node (ref "R18") (pin "3") (pinfunction "3_3") (pintype "passive"))
      (node (ref "U3") (pin "1") (pinfunction "GAIN_1") (pintype "passive"))
    )
    (net (code "59") (name "Net-(R19-Pad3)") (class "Default")
      (node (ref "R19") (pin "3") (pinfunction "3_3") (pintype "passive"))
      (node (ref "U7") (pin "1") (pinfunction "GAIN_1") (pintype "passive"))
    )
    (net (code "60") (name "Net-(R24-Pad3)") (class "Default")
      (node (ref "R24") (pin "3") (pinfunction "3_3") (pintype "passive"))
      (node (ref "U4") (pin "1") (pinfunction "GAIN_1") (pintype "passive"))
    )
    (net (code "61") (name "Net-(R25-Pad3)") (class "Default")
      (node (ref "R25") (pin "3") (pinfunction "3_3") (pintype "passive"))
      (node (ref "U8") (pin "1") (pinfunction "GAIN_1") (pintype "passive"))
    )
    (net (code "62") (name "Net-(U1-BYPASS)") (class "Default")
      (node (ref "C9") (pin "2") (pinfunction "2_2") (pintype "passive"))
      (node (ref "U1") (pin "7") (pinfunction "BYPASS_7") (pintype "passive"))
    )
    (net (code "63") (name "Net-(U1-IN+)") (class "Default")
      (node (ref "C3") (pin "2") (pinfunction "2_2") (pintype "passive"))
      (node (ref "U1") (pin "3") (pinfunction "IN+_3") (pintype "input"))
    )
    (net (code "64") (name "Net-(U1-VOUT)") (class "Default")
      (node (ref "C1") (pin "1") (pinfunction "1_1") (pintype "passive"))
      (node (ref "C7") (pin "2") (pinfunction "2_2") (pintype "passive"))
      (node (ref "U1") (pin "5") (pinfunction "VOUT_5") (pintype "output"))
    )
    (net (code "65") (name "Net-(U2-BYPASS)") (class "Default")
      (node (ref "C23") (pin "2") (pinfunction "2_2") (pintype "passive"))
      (node (ref "U2") (pin "7") (pinfunction "BYPASS_7") (pintype "passive"))
    )
    (net (code "66") (name "Net-(U2-IN+)") (class "Default")
      (node (ref "C17") (pin "2") (pinfunction "2_2") (pintype "passive"))
      (node (ref "U2") (pin "3") (pinfunction "IN+_3") (pintype "input"))
    )
    (net (code "67") (name "Net-(U2-VOUT)") (class "Default")
      (node (ref "C16") (pin "1") (pinfunction "1_1") (pintype "passive"))
      (node (ref "C20") (pin "2") (pinfunction "2_2") (pintype "passive"))
      (node (ref "U2") (pin "5") (pinfunction "VOUT_5") (pintype "output"))
    )
    (net (code "68") (name "Net-(U3-BYPASS)") (class "Default")
      (node (ref "C39") (pin "2") (pinfunction "2_2") (pintype "passive"))
      (node (ref "U3") (pin "7") (pinfunction "BYPASS_7") (pintype "passive"))
    )
    (net (code "69") (name "Net-(U3-IN+)") (class "Default")
      (node (ref "C32") (pin "2") (pinfunction "2_2") (pintype "passive"))
      (node (ref "U3") (pin "3") (pinfunction "IN+_3") (pintype "input"))
    )
    (net (code "70") (name "Net-(U3-VOUT)") (class "Default")
      (node (ref "C31") (pin "1") (pinfunction "1_1") (pintype "passive"))
      (node (ref "C36") (pin "2") (pinfunction "2_2") (pintype "passive"))
      (node (ref "U3") (pin "5") (pinfunction "VOUT_5") (pintype "output"))
    )
    (net (code "71") (name "Net-(U4-BYPASS)") (class "Default")
      (node (ref "C53") (pin "2") (pinfunction "2_2") (pintype "passive"))
      (node (ref "U4") (pin "7") (pinfunction "BYPASS_7") (pintype "passive"))
    )
    (net (code "72") (name "Net-(U4-IN+)") (class "Default")
      (node (ref "C47") (pin "2") (pinfunction "2_2") (pintype "passive"))
      (node (ref "U4") (pin "3") (pinfunction "IN+_3") (pintype "input"))
    )
    (net (code "73") (name "Net-(U4-VOUT)") (class "Default")
      (node (ref "C45") (pin "1") (pinfunction "1_1") (pintype "passive"))
      (node (ref "C50") (pin "2") (pinfunction "2_2") (pintype "passive"))
      (node (ref "U4") (pin "5") (pinfunction "VOUT_5") (pintype "output"))
    )
    (net (code "74") (name "Net-(U5-BYPASS)") (class "Default")
      (node (ref "C10") (pin "2") (pinfunction "2_2") (pintype "passive"))
      (node (ref "U5") (pin "7") (pinfunction "BYPASS_7") (pintype "passive"))
    )
    (net (code "75") (name "Net-(U5-IN+)") (class "Default")
      (node (ref "C4") (pin "2") (pinfunction "2_2") (pintype "passive"))
      (node (ref "U5") (pin "3") (pinfunction "IN+_3") (pintype "input"))
    )
    (net (code "76") (name "Net-(U5-VOUT)") (class "Default")
      (node (ref "C2") (pin "1") (pinfunction "1_1") (pintype "passive"))
      (node (ref "C8") (pin "2") (pinfunction "2_2") (pintype "passive"))
      (node (ref "U5") (pin "5") (pinfunction "VOUT_5") (pintype "output"))
    )
    (net (code "77") (name "Net-(U6-BYPASS)") (class "Default")
      (node (ref "C24") (pin "2") (pinfunction "2_2") (pintype "passive"))
      (node (ref "U6") (pin "7") (pinfunction "BYPASS_7") (pintype "passive"))
    )
    (net (code "78") (name "Net-(U6-IN+)") (class "Default")
      (node (ref "C18") (pin "2") (pinfunction "2_2") (pintype "passive"))
      (node (ref "U6") (pin "3") (pinfunction "IN+_3") (pintype "input"))
    )
    (net (code "79") (name "Net-(U6-VOUT)") (class "Default")
      (node (ref "C15") (pin "1") (pinfunction "1_1") (pintype "passive"))
      (node (ref "C22") (pin "2") (pinfunction "2_2") (pintype "passive"))
      (node (ref "U6") (pin "5") (pinfunction "VOUT_5") (pintype "output"))
    )
    (net (code "80") (name "Net-(U7-BYPASS)") (class "Default")
      (node (ref "C40") (pin "2") (pinfunction "2_2") (pintype "passive"))
      (node (ref "U7") (pin "7") (pinfunction "BYPASS_7") (pintype "passive"))
    )
    (net (code "81") (name "Net-(U7-IN+)") (class "Default")
      (node (ref "C34") (pin "2") (pinfunction "2_2") (pintype "passive"))
      (node (ref "U7") (pin "3") (pinfunction "IN+_3") (pintype "input"))
    )
    (net (code "82") (name "Net-(U7-VOUT)") (class "Default")
      (node (ref "C33") (pin "1") (pinfunction "1_1") (pintype "passive"))
      (node (ref "C38") (pin "2") (pinfunction "2_2") (pintype "passive"))
      (node (ref "U7") (pin "5") (pinfunction "VOUT_5") (pintype "output"))
    )
    (net (code "83") (name "Net-(U8-BYPASS)") (class "Default")
      (node (ref "C54") (pin "2") (pinfunction "2_2") (pintype "passive"))
      (node (ref "U8") (pin "7") (pinfunction "BYPASS_7") (pintype "passive"))
    )
    (net (code "84") (name "Net-(U8-IN+)") (class "Default")
      (node (ref "C48") (pin "2") (pinfunction "2_2") (pintype "passive"))
      (node (ref "U8") (pin "3") (pinfunction "IN+_3") (pintype "input"))
    )
    (net (code "85") (name "Net-(U8-VOUT)") (class "Default")
      (node (ref "C46") (pin "1") (pinfunction "1_1") (pintype "passive"))
      (node (ref "C52") (pin "2") (pinfunction "2_2") (pintype "passive"))
      (node (ref "U8") (pin "5") (pinfunction "VOUT_5") (pintype "output"))
    )
  )
)
